# SPI_IFC.net
KiCad netlist of a schematic drawn in Altium Designer
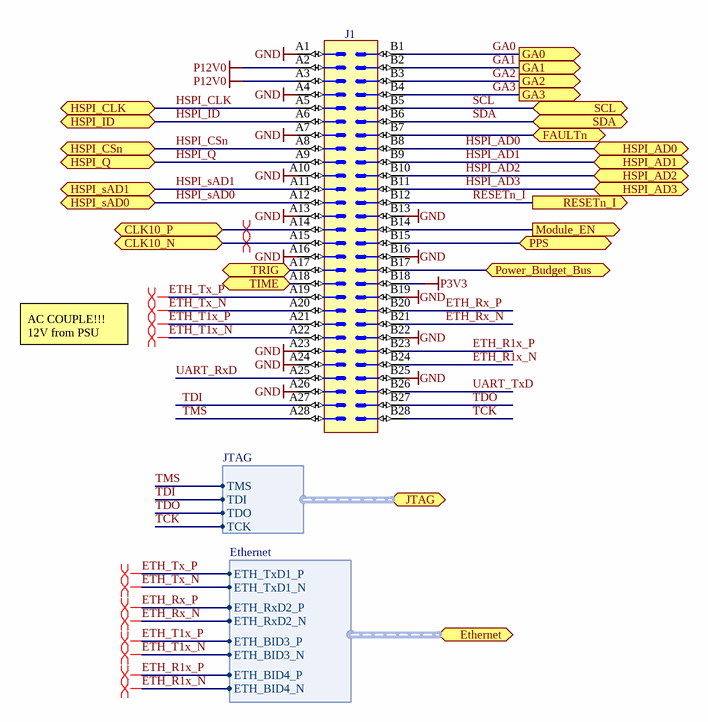
[diagram p0: SPI_IFC.SchDoc]

(export (version "E")
  (design (tool "Eeschema 10.0.6"))
  (components
    (comp (ref "J1")
      (value "~")
      (footprint "AMPHENOL_MINI-COOL-56P")
      (description "64 contacts Board Eddge PCI Express x4 Socket")
      (fields
        (field (name "PART NUMBER") "AMPHENOL_MINI-Cool-56P")
        (field (name "MANUFACTURER") "AMPHENOL")
        (field (name "AUTHOR") "CERN DEM HF")
      )
      (libsource (lib "Connectors") (part "AMPHENOL_MINI-Cool-56P"))
    )
  )
  (nets
    (net (code "3") (name "/CLK10_N") (class "Default")
      (node (ref "J1") (pin "A15") (pinfunction "A15_A15") (pintype "bidirectional"))
    )
    (net (code "4") (name "/CLK10_P") (class "Default")
      (node (ref "J1") (pin "A14") (pinfunction "A14_A14") (pintype "bidirectional"))
    )
    (net (code "5") (name "/ETH_R1x_N") (class "Default")
      (node (ref "J1") (pin "B24") (pinfunction "B24_B24") (pintype "bidirectional"))
    )
    (net (code "6") (name "/ETH_R1x_P") (class "Default")
      (node (ref "J1") (pin "B23") (pinfunction "B23_B23") (pintype "bidirectional"))
    )
    (net (code "7") (name "/ETH_Rx_N") (class "Default")
      (node (ref "J1") (pin "B21") (pinfunction "B21_B21") (pintype "bidirectional"))
    )
    (net (code "8") (name "/ETH_Rx_P") (class "Default")
      (node (ref "J1") (pin "B20") (pinfunction "B20_B20") (pintype "bidirectional"))
    )
    (net (code "9") (name "/ETH_T1x_N") (class "Default")
      (node (ref "J1") (pin "A22") (pinfunction "A22_A22") (pintype "bidirectional"))
    )
    (net (code "10") (name "/ETH_T1x_P") (class "Default")
      (node (ref "J1") (pin "A21") (pinfunction "A21_A21") (pintype "bidirectional"))
    )
    (net (code "11") (name "/ETH_Tx_N") (class "Default")
      (node (ref "J1") (pin "A20") (pinfunction "A20_A20") (pintype "bidirectional"))
    )
    (net (code "12") (name "/ETH_Tx_P") (class "Default")
      (node (ref "J1") (pin "A19") (pinfunction "A19_A19") (pintype "bidirectional"))
    )
    (net (code "13") (name "/FAULTn") (class "Default")
      (node (ref "J1") (pin "B7") (pinfunction "B7_B7") (pintype "bidirectional"))
    )
    (net (code "14") (name "/GA0") (class "Default")
      (node (ref "J1") (pin "B1") (pinfunction "B1_B1") (pintype "bidirectional"))
    )
    (net (code "15") (name "/GA1") (class "Default")
      (node (ref "J1") (pin "B2") (pinfunction "B2_B2") (pintype "bidirectional"))
    )
    (net (code "16") (name "/GA2") (class "Default")
      (node (ref "J1") (pin "B3") (pinfunction "B3_B3") (pintype "bidirectional"))
    )
    (net (code "17") (name "/GA3") (class "Default")
      (node (ref "J1") (pin "B4") (pinfunction "B4_B4") (pintype "bidirectional"))
    )
    (net (code "18") (name "/HSPI_AD0") (class "Default")
      (node (ref "J1") (pin "B8") (pinfunction "B8_B8") (pintype "bidirectional"))
    )
    (net (code "19") (name "/HSPI_AD1") (class "Default")
      (node (ref "J1") (pin "B9") (pinfunction "B9_B9") (pintype "bidirectional"))
    )
    (net (code "20") (name "/HSPI_AD2") (class "Default")
      (node (ref "J1") (pin "B10") (pinfunction "B10_B10") (pintype "bidirectional"))
    )
    (net (code "21") (name "/HSPI_AD3") (class "Default")
      (node (ref "J1") (pin "B11") (pinfunction "B11_B11") (pintype "bidirectional"))
    )
    (net (code "22") (name "/HSPI_CLK") (class "Default")
      (node (ref "J1") (pin "A5") (pinfunction "A5_A5") (pintype "bidirectional"))
    )
    (net (code "23") (name "/HSPI_CSn") (class "Default")
      (node (ref "J1") (pin "A8") (pinfunction "A8_A8") (pintype "bidirectional"))
    )
    (net (code "24") (name "/HSPI_ID") (class "Default")
      (node (ref "J1") (pin "A6") (pinfunction "A6_A6") (pintype "bidirectional"))
    )
    (net (code "25") (name "/HSPI_Q") (class "Default")
      (node (ref "J1") (pin "A9") (pinfunction "A9_A9") (pintype "bidirectional"))
    )
    (net (code "26") (name "/HSPI_sAD0") (class "Default")
      (node (ref "J1") (pin "A12") (pinfunction "A12_A12") (pintype "bidirectional"))
    )
    (net (code "27") (name "/HSPI_sAD1") (class "Default")
      (node (ref "J1") (pin "A11") (pinfunction "A11_A11") (pintype "bidirectional"))
    )
    (net (code "28") (name "/Module_EN") (class "Default")
      (node (ref "J1") (pin "B14") (pinfunction "B14_B14") (pintype "bidirectional"))
    )
    (net (code "29") (name "/PPS") (class "Default")
      (node (ref "J1") (pin "B15") (pinfunction "B15_B15") (pintype "bidirectional"))
    )
    (net (code "30") (name "/Power_Budget_Bus") (class "Default")
      (node (ref "J1") (pin "B17") (pinfunction "B17_B17") (pintype "bidirectional"))
    )
    (net (code "31") (name "/RESETn_I") (class "Default")
      (node (ref "J1") (pin "B12") (pinfunction "B12_B12") (pintype "bidirectional"))
    )
    (net (code "32") (name "/SCL") (class "Default")
      (node (ref "J1") (pin "B5") (pinfunction "B5_B5") (pintype "bidirectional"))
    )
    (net (code "33") (name "/SDA") (class "Default")
      (node (ref "J1") (pin "B6") (pinfunction "B6_B6") (pintype "bidirectional"))
    )
    (net (code "34") (name "/TCK") (class "Default")
      (node (ref "J1") (pin "B28") (pinfunction "B28_B28") (pintype "bidirectional"))
    )
    (net (code "35") (name "/TDI") (class "Default")
      (node (ref "J1") (pin "A27") (pinfunction "A27_A27") (pintype "bidirectional"))
    )
    (net (code "36") (name "/TDO") (class "Default")
      (node (ref "J1") (pin "B27") (pinfunction "B27_B27") (pintype "bidirectional"))
    )
    (net (code "37") (name "/TIME") (class "Default")
      (node (ref "J1") (pin "A18") (pinfunction "A18_A18") (pintype "bidirectional"))
    )
    (net (code "38") (name "/TMS") (class "Default")
      (node (ref "J1") (pin "A28") (pinfunction "A28_A28") (pintype "bidirectional"))
    )
    (net (code "39") (name "/TRIG") (class "Default")
      (node (ref "J1") (pin "A17") (pinfunction "A17_A17") (pintype "bidirectional"))
    )
    (net (code "40") (name "/UART_RxD") (class "Default")
      (node (ref "J1") (pin "A25") (pinfunction "A25_A25") (pintype "bidirectional"))
    )
    (net (code "41") (name "/UART_TxD") (class "Default")
      (node (ref "J1") (pin "B26") (pinfunction "B26_B26") (pintype "bidirectional"))
    )
    (net (code "44") (name "GND") (class "Default")
      (node (ref "J1") (pin "A1") (pinfunction "A1_A1") (pintype "bidirectional"))
      (node (ref "J1") (pin "A10") (pinfunction "A10_A10") (pintype "bidirectional"))
      (node (ref "J1") (pin "A13") (pinfunction "A13_A13") (pintype "bidirectional"))
      (node (ref "J1") (pin "A16") (pinfunction "A16_A16") (pintype "bidirectional"))
      (node (ref "J1") (pin "A23") (pinfunction "A23_A23") (pintype "bidirectional"))
      (node (ref "J1") (pin "A24") (pinfunction "A24_A24") (pintype "bidirectional"))
      (node (ref "J1") (pin "A26") (pinfunction "A26_A26") (pintype "bidirectional"))
      (node (ref "J1") (pin "A4") (pinfunction "A4_A4") (pintype "bidirectional"))
      (node (ref "J1") (pin "A7") (pinfunction "A7_A7") (pintype "bidirectional"))
      (node (ref "J1") (pin "B13") (pinfunction "B13_B13") (pintype "bidirectional"))
      (node (ref "J1") (pin "B16") (pinfunction "B16_B16") (pintype "bidirectional"))
      (node (ref "J1") (pin "B19") (pinfunction "B19_B19") (pintype "bidirectional"))
      (node (ref "J1") (pin "B22") (pinfunction "B22_B22") (pintype "bidirectional"))
      (node (ref "J1") (pin "B25") (pinfunction "B25_B25") (pintype "bidirectional"))
    )
    (net (code "45") (name "P3V3") (class "Default")
      (node (ref "J1") (pin "B18") (pinfunction "B18_B18") (pintype "bidirectional"))
    )
    (net (code "46") (name "P12V0") (class "Default")
      (node (ref "J1") (pin "A2") (pinfunction "A2_A2") (pintype "bidirectional"))
      (node (ref "J1") (pin "A3") (pinfunction "A3_A3") (pintype "bidirectional"))
    )
  )
)
